# z0-probe-v6.net
KiCad netlist of a schematic drawn in EAGLE
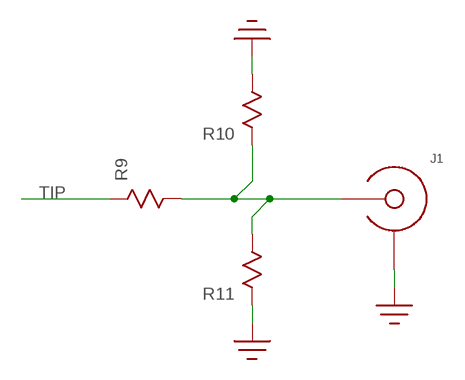
[diagram p0: schematic, sheet 1]

(export (version "E")
  (design (tool "Eeschema 10.0.6"))
  (components
    (comp (ref "J1")
      (value "SMA-EDGE-LAUNCH")
      (footprint "eagle-import:SMA_EDGE_LAUNCH_2L_4020_TAPER_FIXED")
      (libsource (lib "eagle-import") (part "SMA-EDGE-LAUNCH"))
    )
    (comp (ref "R9")
      (value "R0603-TIGHT")
      (footprint "eagle-import:0603_TIGHT")
      (libsource (lib "eagle-import") (part "R0603-TIGHT"))
    )
    (comp (ref "R10")
      (value "R0603-TIGHT")
      (footprint "eagle-import:0603_TIGHT")
      (libsource (lib "eagle-import") (part "R0603-TIGHT"))
    )
    (comp (ref "R11")
      (value "R0603-TIGHT")
      (footprint "eagle-import:0603_TIGHT")
      (libsource (lib "eagle-import") (part "R0603-TIGHT"))
    )
  )
  (nets
    (net (code "1") (name "/TIP") (class "Default")
      (node (ref "R9") (pin "P$1") (pinfunction "P$3_P$1") (pintype "bidirectional"))
    )
    (net (code "2") (name "GND") (class "Default")
      (node (ref "J1") (pin "BOTTOM_GND") (pinfunction "SHIELD_BOTTOM_GND") (pintype "bidirectional"))
      (node (ref "J1") (pin "GND@1") (pinfunction "SHIELD_GND@1") (pintype "bidirectional"))
      (node (ref "J1") (pin "GND@14") (pinfunction "SHIELD_GND@14") (pintype "bidirectional"))
      (node (ref "J1") (pin "GND@15") (pinfunction "SHIELD_GND@15") (pintype "bidirectional"))
      (node (ref "J1") (pin "GND@16") (pinfunction "SHIELD_GND@16") (pintype "bidirectional"))
      (node (ref "J1") (pin "GND@17") (pinfunction "SHIELD_GND@17") (pintype "bidirectional"))
      (node (ref "J1") (pin "GND@2") (pinfunction "SHIELD_GND@2") (pintype "bidirectional"))
      (node (ref "J1") (pin "GND@3") (pinfunction "SHIELD_GND@3") (pintype "bidirectional"))
      (node (ref "J1") (pin "GND@4") (pinfunction "SHIELD_GND@4") (pintype "bidirectional"))
      (node (ref "J1") (pin "GND@5") (pinfunction "SHIELD_GND@5") (pintype "bidirectional"))
      (node (ref "J1") (pin "GND@6") (pinfunction "SHIELD_GND@6") (pintype "bidirectional"))
      (node (ref "J1") (pin "GND@7") (pinfunction "SHIELD_GND@7") (pintype "bidirectional"))
      (node (ref "J1") (pin "GND@8") (pinfunction "SHIELD_GND@8") (pintype "bidirectional"))
      (node (ref "J1") (pin "GND_PAD1") (pinfunction "SHIELD_GND_PAD1") (pintype "bidirectional"))
      (node (ref "J1") (pin "GND_PAD2") (pinfunction "SHIELD_GND_PAD2") (pintype "bidirectional"))
      (node (ref "J1") (pin "P$1") (pinfunction "SHIELD_P$1") (pintype "bidirectional"))
      (node (ref "J1") (pin "P$2") (pinfunction "SHIELD_P$2") (pintype "bidirectional"))
      (node (ref "R10") (pin "P$2") (pinfunction "P$4_P$2") (pintype "bidirectional"))
      (node (ref "R11") (pin "P$1") (pinfunction "P$3_P$1") (pintype "bidirectional"))
    )
    (net (code "3") (name "Net-(R10-P$3)") (class "Default")
      (node (ref "J1") (pin "CENTER@1") (pinfunction "CENTER_CENTER@1") (pintype "bidirectional"))
      (node (ref "J1") (pin "P$3") (pinfunction "CENTER_P$3") (pintype "bidirectional"))
      (node (ref "R10") (pin "P$1") (pinfunction "P$3_P$1") (pintype "bidirectional"))
      (node (ref "R11") (pin "P$2") (pinfunction "P$4_P$2") (pintype "bidirectional"))
      (node (ref "R9") (pin "P$2") (pinfunction "P$4_P$2") (pintype "bidirectional"))
    )
  )
)
